# QSPI.net
KiCad netlist of a schematic drawn in Altium Designer
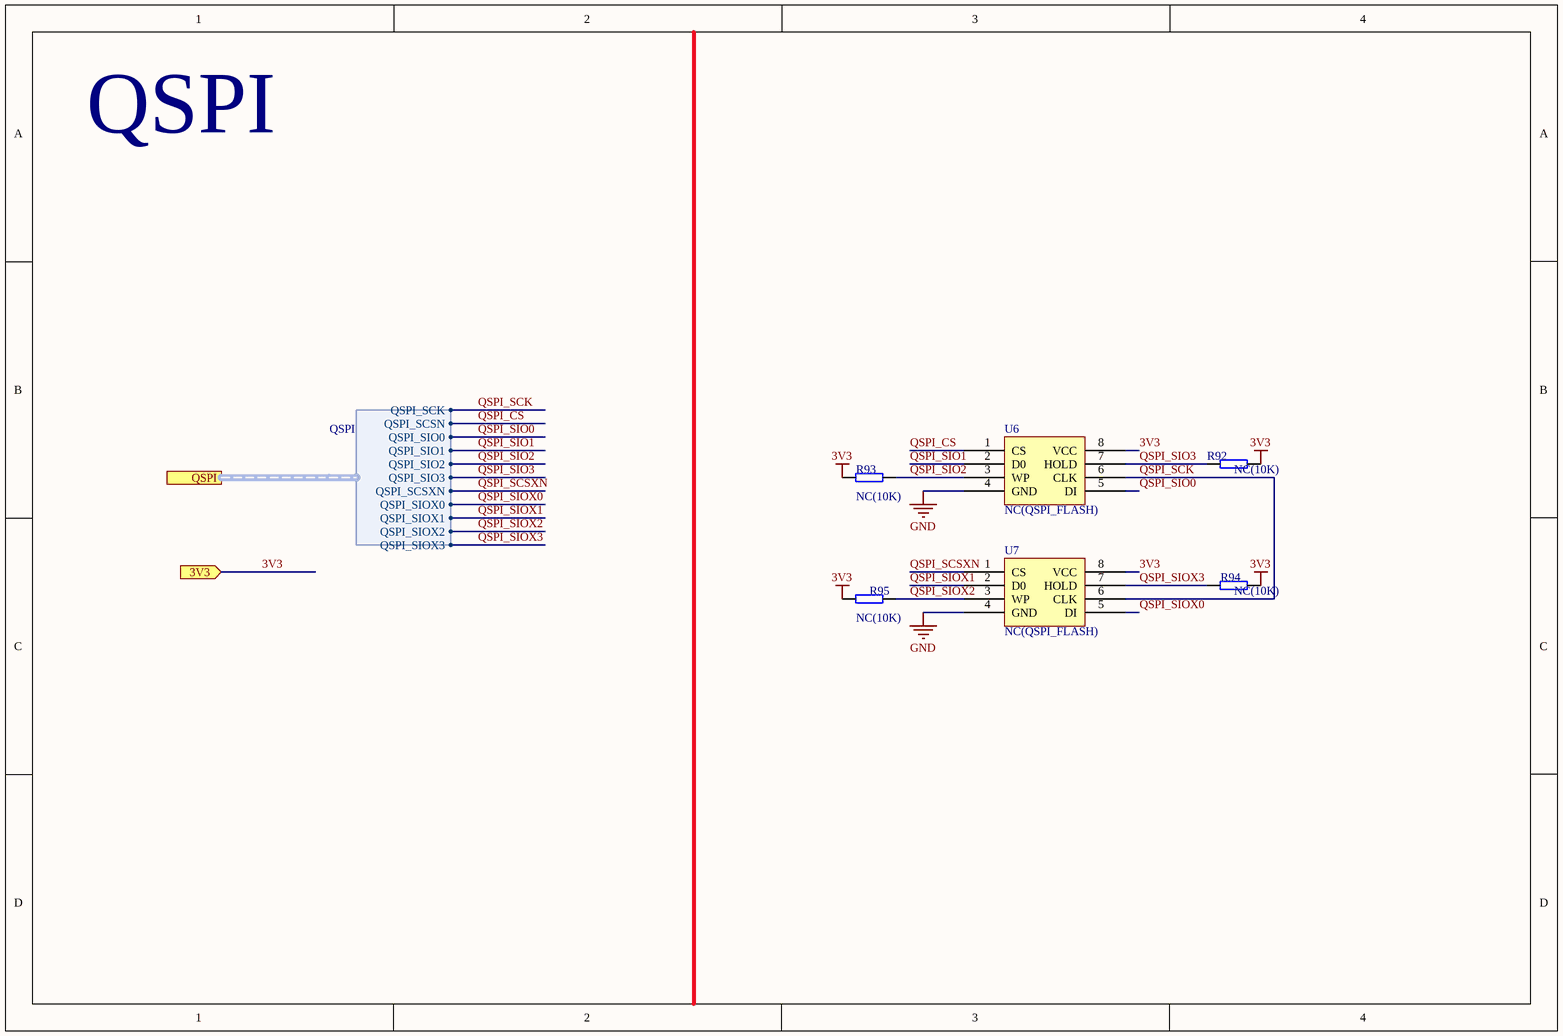
[diagram p0: QSPI.SchDoc]

(export (version "E")
  (design (tool "Eeschema 10.0.6"))
  (components
    (comp (ref "R92") (value "NC(10K)") (footprint "0402") (libsource (lib "*") (part "RES")))
    (comp (ref "R93") (value "NC(10K)") (footprint "0402") (libsource (lib "*") (part "RES")))
    (comp (ref "R94") (value "NC(10K)") (footprint "0402") (libsource (lib "*") (part "RES")))
    (comp (ref "R95") (value "NC(10K)") (footprint "0402") (libsource (lib "*") (part "RES")))
    (comp (ref "U6")
      (value "NC(QSPI_FLASH)")
      (footprint "SOIC-8_208mil")
      (libsource (lib "wch_sch_others") (part "W25Q64"))
    )
    (comp (ref "U7")
      (value "NC(QSPI_FLASH)")
      (footprint "SOIC-8_208mil")
      (libsource (lib "wch_sch_others") (part "W25Q64"))
    )
  )
  (nets
    (net (code "2") (name "/QSPI_CS") (class "Default")
      (node (ref "U6") (pin "1") (pinfunction "CS_1") (pintype "passive"))
    )
    (net (code "3") (name "/QSPI_SCK") (class "Default")
      (node (ref "U6") (pin "6") (pinfunction "CLK_6") (pintype "passive"))
      (node (ref "U7") (pin "6") (pinfunction "CLK_6") (pintype "passive"))
    )
    (net (code "4") (name "/QSPI_SCSXN") (class "Default")
      (node (ref "U7") (pin "1") (pinfunction "CS_1") (pintype "passive"))
    )
    (net (code "5") (name "/QSPI_SIO0") (class "Default")
      (node (ref "U6") (pin "5") (pinfunction "DI_5") (pintype "passive"))
    )
    (net (code "6") (name "/QSPI_SIO1") (class "Default")
      (node (ref "U6") (pin "2") (pinfunction "D0_2") (pintype "passive"))
    )
    (net (code "7") (name "/QSPI_SIO2") (class "Default")
      (node (ref "R93") (pin "1") (pintype "passive"))
      (node (ref "U6") (pin "3") (pinfunction "WP_3") (pintype "passive"))
    )
    (net (code "8") (name "/QSPI_SIO3") (class "Default")
      (node (ref "R92") (pin "2") (pintype "passive"))
      (node (ref "U6") (pin "7") (pinfunction "HOLD_7") (pintype "passive"))
    )
    (net (code "9") (name "/QSPI_SIOX0") (class "Default")
      (node (ref "U7") (pin "5") (pinfunction "DI_5") (pintype "passive"))
    )
    (net (code "10") (name "/QSPI_SIOX1") (class "Default")
      (node (ref "U7") (pin "2") (pinfunction "D0_2") (pintype "passive"))
    )
    (net (code "11") (name "/QSPI_SIOX2") (class "Default")
      (node (ref "R95") (pin "1") (pintype "passive"))
      (node (ref "U7") (pin "3") (pinfunction "WP_3") (pintype "passive"))
    )
    (net (code "12") (name "/QSPI_SIOX3") (class "Default")
      (node (ref "R94") (pin "2") (pintype "passive"))
      (node (ref "U7") (pin "7") (pinfunction "HOLD_7") (pintype "passive"))
    )
    (net (code "14") (name "3V3") (class "Default")
      (node (ref "R92") (pin "1") (pintype "passive"))
      (node (ref "R93") (pin "2") (pintype "passive"))
      (node (ref "R94") (pin "1") (pintype "passive"))
      (node (ref "R95") (pin "2") (pintype "passive"))
      (node (ref "U6") (pin "8") (pinfunction "VCC_8") (pintype "passive"))
      (node (ref "U7") (pin "8") (pinfunction "VCC_8") (pintype "passive"))
    )
    (net (code "15") (name "GND") (class "Default")
      (node (ref "U6") (pin "4") (pinfunction "GND_4") (pintype "passive"))
      (node (ref "U7") (pin "4") (pinfunction "GND_4") (pintype "passive"))
    )
  )
)
